# VIC20_SExp.net
KiCad netlist of a schematic drawn in EAGLE
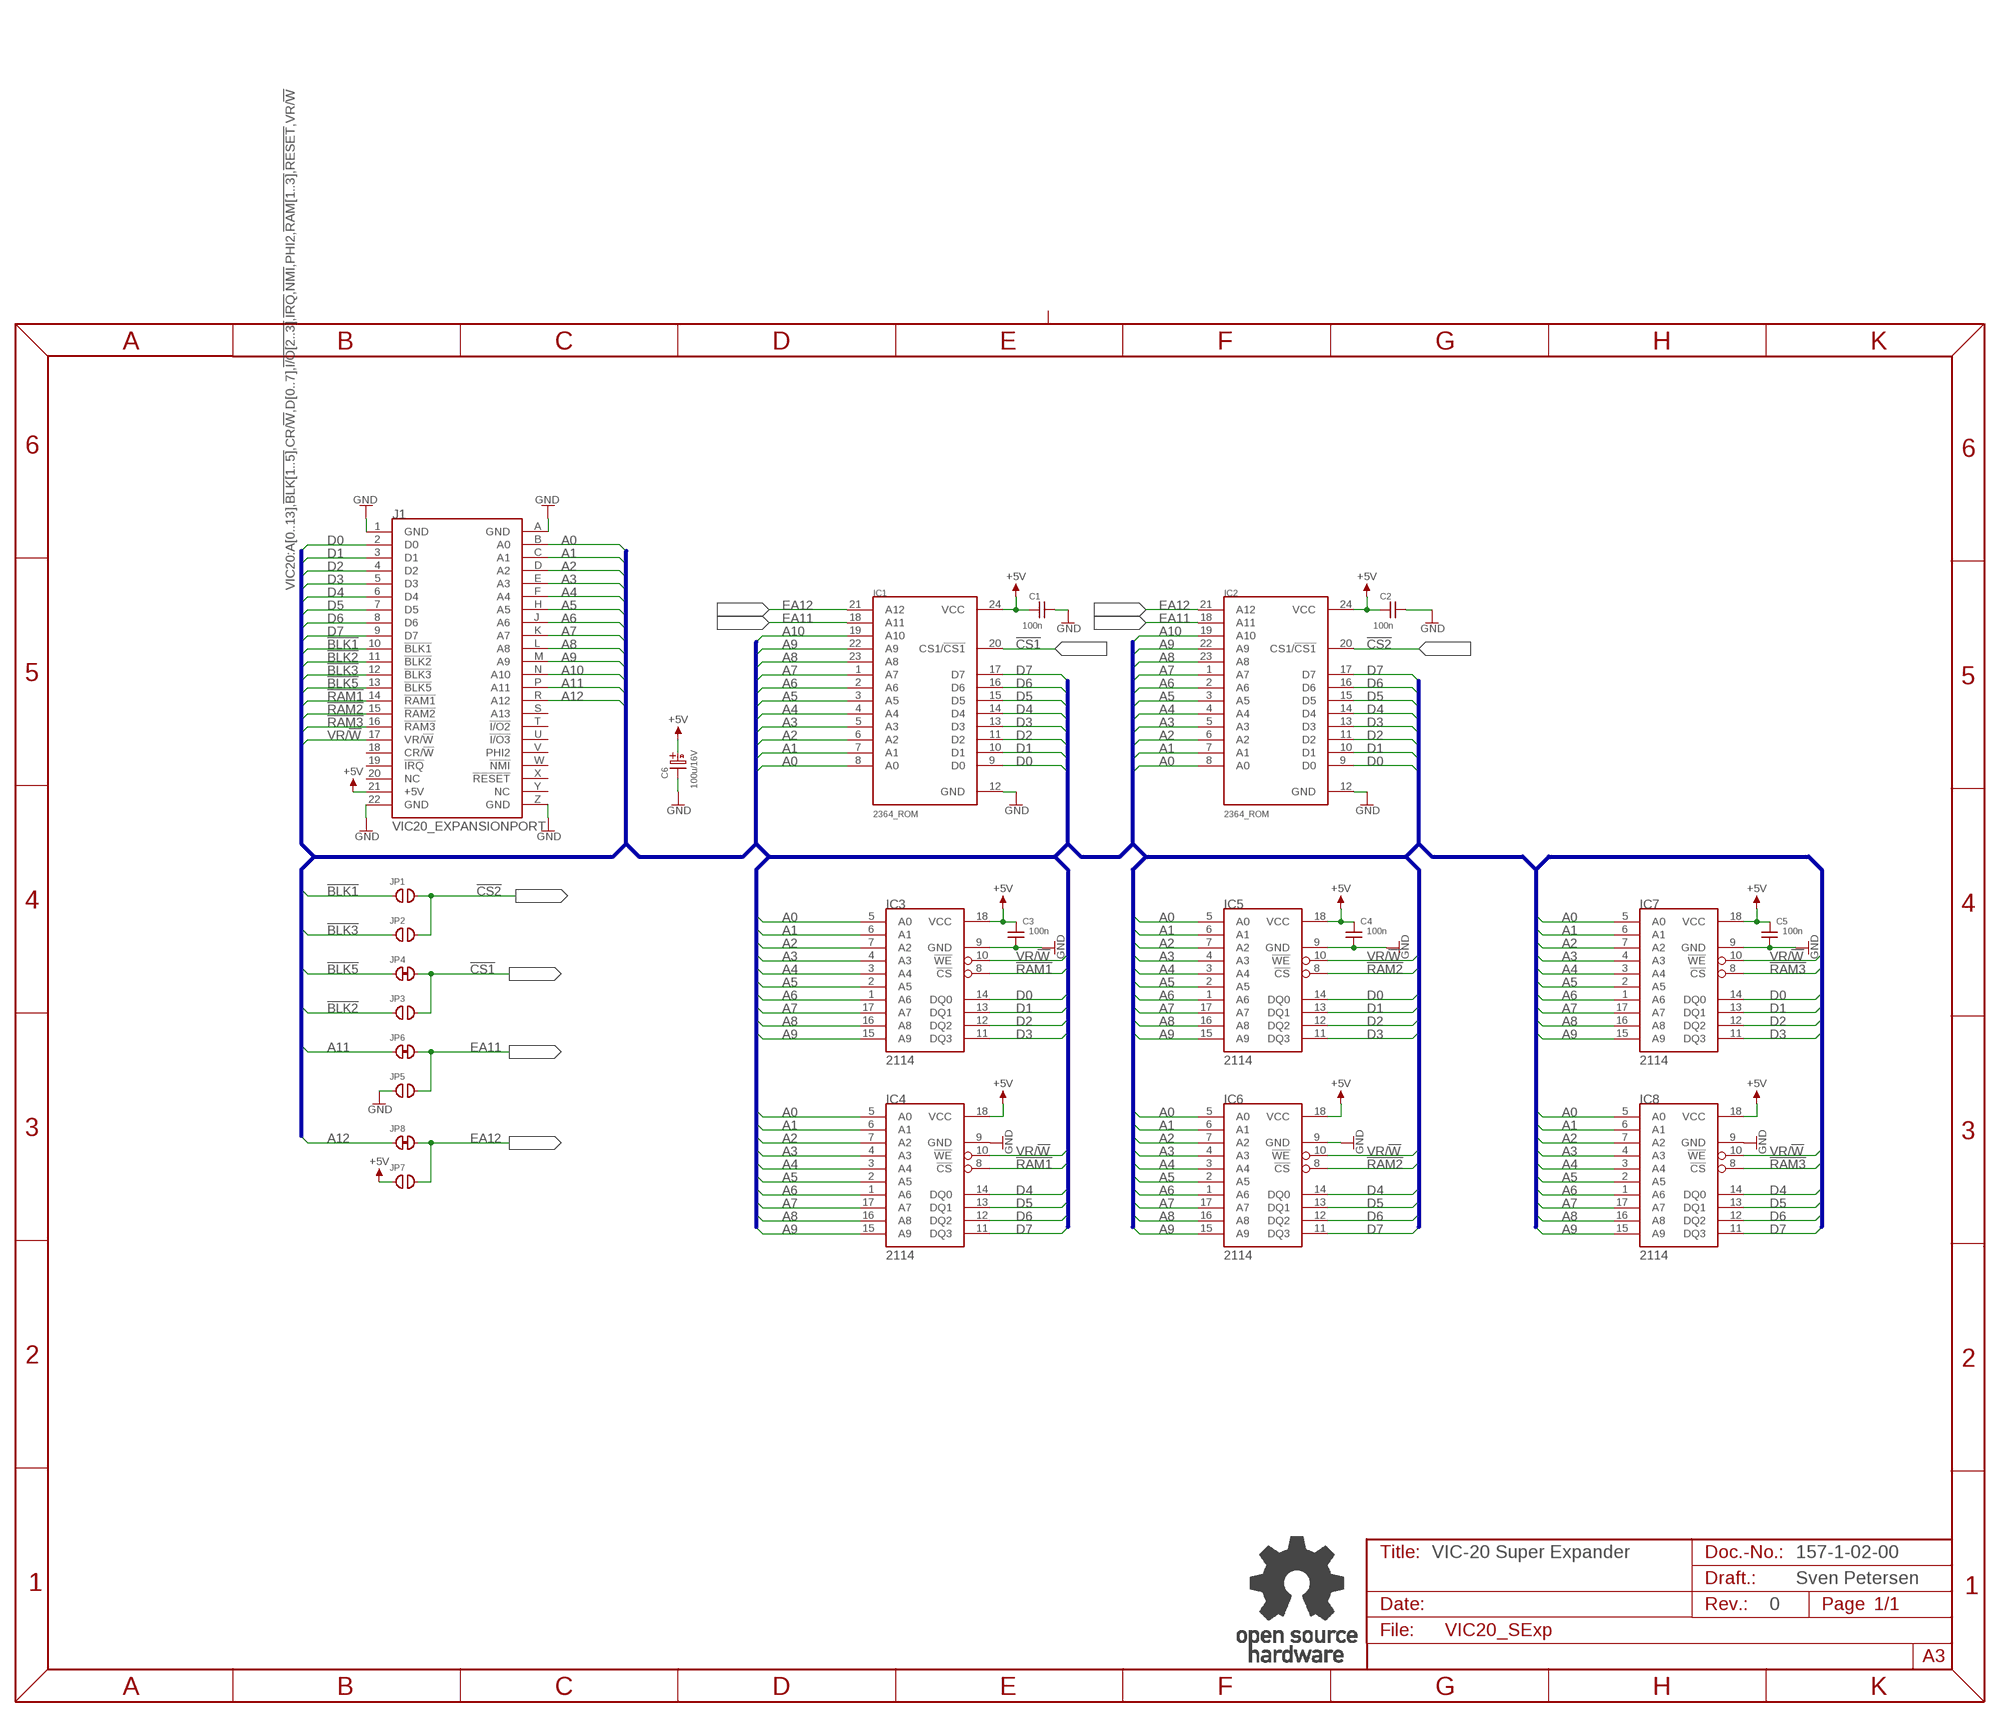
[diagram p0: schematic, sheet 1]

(export (version "E")
  (design (tool "Eeschema 10.0.6"))
  (components
    (comp (ref "C1")
      (value "100n")
      (footprint "eagle-import:C-2,5")
      (libsource (lib "eagle-import") (part "CAP01"))
    )
    (comp (ref "C2")
      (value "100n")
      (footprint "eagle-import:C-2,5")
      (libsource (lib "eagle-import") (part "CAP01"))
    )
    (comp (ref "C3")
      (value "100n")
      (footprint "eagle-import:C-2,5")
      (libsource (lib "eagle-import") (part "CAP01"))
    )
    (comp (ref "C4")
      (value "100n")
      (footprint "eagle-import:C-2,5")
      (libsource (lib "eagle-import") (part "CAP01"))
    )
    (comp (ref "C5")
      (value "100n")
      (footprint "eagle-import:C-2,5")
      (libsource (lib "eagle-import") (part "CAP01"))
    )
    (comp (ref "C6")
      (value "100u/16V")
      (footprint "eagle-import:C07_2,5")
      (libsource (lib "eagle-import") (part "C07/2,5"))
    )
    (comp (ref "IC1")
      (value "2364_ROM")
      (footprint "eagle-import:DIL24-6")
      (libsource (lib "eagle-import") (part "2364_ROM"))
    )
    (comp (ref "IC2")
      (value "2364_ROM")
      (footprint "eagle-import:DIL24-6")
      (libsource (lib "eagle-import") (part "2364_ROM"))
    )
    (comp (ref "IC3")
      (value "2114")
      (footprint "eagle-import:DIL18")
      (libsource (lib "eagle-import") (part "2114"))
    )
    (comp (ref "IC4")
      (value "2114")
      (footprint "eagle-import:DIL18")
      (libsource (lib "eagle-import") (part "2114"))
    )
    (comp (ref "IC5")
      (value "2114")
      (footprint "eagle-import:DIL18")
      (libsource (lib "eagle-import") (part "2114"))
    )
    (comp (ref "IC6")
      (value "2114")
      (footprint "eagle-import:DIL18")
      (libsource (lib "eagle-import") (part "2114"))
    )
    (comp (ref "IC7")
      (value "2114")
      (footprint "eagle-import:DIL18")
      (libsource (lib "eagle-import") (part "2114"))
    )
    (comp (ref "IC8")
      (value "2114")
      (footprint "eagle-import:DIL18")
      (libsource (lib "eagle-import") (part "2114"))
    )
    (comp (ref "J1")
      (value "VIC20_EXPANSIONPORT")
      (footprint "eagle-import:VIC20_EXPANSION")
      (libsource (lib "eagle-import") (part "VIC20_EXPANSIONPORT"))
    )
    (comp (ref "JP1")
      (value "OPEN")
      (footprint "eagle-import:CP_OP")
      (libsource (lib "eagle-import") (part "OPEN"))
    )
    (comp (ref "JP2")
      (value "OPEN")
      (footprint "eagle-import:CP_OP")
      (libsource (lib "eagle-import") (part "OPEN"))
    )
    (comp (ref "JP3")
      (value "OPEN")
      (footprint "eagle-import:CP_OP")
      (libsource (lib "eagle-import") (part "OPEN"))
    )
    (comp (ref "JP4")
      (value "CLOSED")
      (footprint "eagle-import:CP_CL")
      (libsource (lib "eagle-import") (part "CLOSED"))
    )
    (comp (ref "JP5")
      (value "OPEN")
      (footprint "eagle-import:CP_OP")
      (libsource (lib "eagle-import") (part "OPEN"))
    )
    (comp (ref "JP6")
      (value "CLOSED")
      (footprint "eagle-import:CP_CL")
      (libsource (lib "eagle-import") (part "CLOSED"))
    )
    (comp (ref "JP7")
      (value "OPEN")
      (footprint "eagle-import:CP_OP")
      (libsource (lib "eagle-import") (part "OPEN"))
    )
    (comp (ref "JP8")
      (value "CLOSED")
      (footprint "eagle-import:CP_CL")
      (libsource (lib "eagle-import") (part "CLOSED"))
    )
    (comp (ref "U$2")
      (value "OPEN_SOURCE_HW")
      (footprint "eagle-import:OPENHW")
      (libsource (lib "eagle-import") (part "OPEN_SOURCE_HW"))
    )
  )
  (nets
    (net (code "6") (name "+5V") (class "Default")
      (node (ref "C1") (pin "1") (pinfunction "1_1") (pintype "passive"))
      (node (ref "C2") (pin "1") (pinfunction "1_1") (pintype "passive"))
      (node (ref "C3") (pin "2") (pinfunction "2_2") (pintype "passive"))
      (node (ref "C4") (pin "2") (pinfunction "2_2") (pintype "passive"))
      (node (ref "C5") (pin "2") (pinfunction "2_2") (pintype "passive"))
      (node (ref "C6") (pin "A") (pinfunction "+_A") (pintype "passive"))
      (node (ref "IC1") (pin "24") (pinfunction "VCC_24") (pintype "power_in"))
      (node (ref "IC2") (pin "24") (pinfunction "VCC_24") (pintype "power_in"))
      (node (ref "IC3") (pin "18") (pinfunction "VCC_18") (pintype "power_in"))
      (node (ref "IC4") (pin "18") (pinfunction "VCC_18") (pintype "power_in"))
      (node (ref "IC5") (pin "18") (pinfunction "VCC_18") (pintype "power_in"))
      (node (ref "IC6") (pin "18") (pinfunction "VCC_18") (pintype "power_in"))
      (node (ref "IC7") (pin "18") (pinfunction "VCC_18") (pintype "power_in"))
      (node (ref "IC8") (pin "18") (pinfunction "VCC_18") (pintype "power_in"))
      (node (ref "J1") (pin "21") (pinfunction "+5V_21") (pintype "power_in"))
      (node (ref "JP7") (pin "1") (pinfunction "1_1") (pintype "passive"))
    )
    (net (code "7") (name "/A0") (class "Default")
      (node (ref "IC1") (pin "8") (pinfunction "A0_8") (pintype "input"))
      (node (ref "IC2") (pin "8") (pinfunction "A0_8") (pintype "input"))
      (node (ref "IC3") (pin "5") (pinfunction "A0_5") (pintype "input"))
      (node (ref "IC4") (pin "5") (pinfunction "A0_5") (pintype "input"))
      (node (ref "IC5") (pin "5") (pinfunction "A0_5") (pintype "input"))
      (node (ref "IC6") (pin "5") (pinfunction "A0_5") (pintype "input"))
      (node (ref "IC7") (pin "5") (pinfunction "A0_5") (pintype "input"))
      (node (ref "IC8") (pin "5") (pinfunction "A0_5") (pintype "input"))
      (node (ref "J1") (pin "B") (pinfunction "A0_B") (pintype "bidirectional"))
    )
    (net (code "8") (name "/A1") (class "Default")
      (node (ref "IC1") (pin "7") (pinfunction "A1_7") (pintype "input"))
      (node (ref "IC2") (pin "7") (pinfunction "A1_7") (pintype "input"))
      (node (ref "IC3") (pin "6") (pinfunction "A1_6") (pintype "input"))
      (node (ref "IC4") (pin "6") (pinfunction "A1_6") (pintype "input"))
      (node (ref "IC5") (pin "6") (pinfunction "A1_6") (pintype "input"))
      (node (ref "IC6") (pin "6") (pinfunction "A1_6") (pintype "input"))
      (node (ref "IC7") (pin "6") (pinfunction "A1_6") (pintype "input"))
      (node (ref "IC8") (pin "6") (pinfunction "A1_6") (pintype "input"))
      (node (ref "J1") (pin "C") (pinfunction "A1_C") (pintype "bidirectional"))
    )
    (net (code "9") (name "/A2") (class "Default")
      (node (ref "IC1") (pin "6") (pinfunction "A2_6") (pintype "input"))
      (node (ref "IC2") (pin "6") (pinfunction "A2_6") (pintype "input"))
      (node (ref "IC3") (pin "7") (pinfunction "A2_7") (pintype "input"))
      (node (ref "IC4") (pin "7") (pinfunction "A2_7") (pintype "input"))
      (node (ref "IC5") (pin "7") (pinfunction "A2_7") (pintype "input"))
      (node (ref "IC6") (pin "7") (pinfunction "A2_7") (pintype "input"))
      (node (ref "IC7") (pin "7") (pinfunction "A2_7") (pintype "input"))
      (node (ref "IC8") (pin "7") (pinfunction "A2_7") (pintype "input"))
      (node (ref "J1") (pin "D") (pinfunction "A2_D") (pintype "bidirectional"))
    )
    (net (code "10") (name "/A3") (class "Default")
      (node (ref "IC1") (pin "5") (pinfunction "A3_5") (pintype "input"))
      (node (ref "IC2") (pin "5") (pinfunction "A3_5") (pintype "input"))
      (node (ref "IC3") (pin "4") (pinfunction "A3_4") (pintype "input"))
      (node (ref "IC4") (pin "4") (pinfunction "A3_4") (pintype "input"))
      (node (ref "IC5") (pin "4") (pinfunction "A3_4") (pintype "input"))
      (node (ref "IC6") (pin "4") (pinfunction "A3_4") (pintype "input"))
      (node (ref "IC7") (pin "4") (pinfunction "A3_4") (pintype "input"))
      (node (ref "IC8") (pin "4") (pinfunction "A3_4") (pintype "input"))
      (node (ref "J1") (pin "E") (pinfunction "A3_E") (pintype "bidirectional"))
    )
    (net (code "11") (name "/A4") (class "Default")
      (node (ref "IC1") (pin "4") (pinfunction "A4_4") (pintype "input"))
      (node (ref "IC2") (pin "4") (pinfunction "A4_4") (pintype "input"))
      (node (ref "IC3") (pin "3") (pinfunction "A4_3") (pintype "input"))
      (node (ref "IC4") (pin "3") (pinfunction "A4_3") (pintype "input"))
      (node (ref "IC5") (pin "3") (pinfunction "A4_3") (pintype "input"))
      (node (ref "IC6") (pin "3") (pinfunction "A4_3") (pintype "input"))
      (node (ref "IC7") (pin "3") (pinfunction "A4_3") (pintype "input"))
      (node (ref "IC8") (pin "3") (pinfunction "A4_3") (pintype "input"))
      (node (ref "J1") (pin "F") (pinfunction "A4_F") (pintype "bidirectional"))
    )
    (net (code "12") (name "/A5") (class "Default")
      (node (ref "IC1") (pin "3") (pinfunction "A5_3") (pintype "input"))
      (node (ref "IC2") (pin "3") (pinfunction "A5_3") (pintype "input"))
      (node (ref "IC3") (pin "2") (pinfunction "A5_2") (pintype "input"))
      (node (ref "IC4") (pin "2") (pinfunction "A5_2") (pintype "input"))
      (node (ref "IC5") (pin "2") (pinfunction "A5_2") (pintype "input"))
      (node (ref "IC6") (pin "2") (pinfunction "A5_2") (pintype "input"))
      (node (ref "IC7") (pin "2") (pinfunction "A5_2") (pintype "input"))
      (node (ref "IC8") (pin "2") (pinfunction "A5_2") (pintype "input"))
      (node (ref "J1") (pin "H") (pinfunction "A5_H") (pintype "bidirectional"))
    )
    (net (code "13") (name "/A6") (class "Default")
      (node (ref "IC1") (pin "2") (pinfunction "A6_2") (pintype "input"))
      (node (ref "IC2") (pin "2") (pinfunction "A6_2") (pintype "input"))
      (node (ref "IC3") (pin "1") (pinfunction "A6_1") (pintype "input"))
      (node (ref "IC4") (pin "1") (pinfunction "A6_1") (pintype "input"))
      (node (ref "IC5") (pin "1") (pinfunction "A6_1") (pintype "input"))
      (node (ref "IC6") (pin "1") (pinfunction "A6_1") (pintype "input"))
      (node (ref "IC7") (pin "1") (pinfunction "A6_1") (pintype "input"))
      (node (ref "IC8") (pin "1") (pinfunction "A6_1") (pintype "input"))
      (node (ref "J1") (pin "J") (pinfunction "A6_J") (pintype "bidirectional"))
    )
    (net (code "14") (name "/A7") (class "Default")
      (node (ref "IC1") (pin "1") (pinfunction "A7_1") (pintype "input"))
      (node (ref "IC2") (pin "1") (pinfunction "A7_1") (pintype "input"))
      (node (ref "IC3") (pin "17") (pinfunction "A7_17") (pintype "input"))
      (node (ref "IC4") (pin "17") (pinfunction "A7_17") (pintype "input"))
      (node (ref "IC5") (pin "17") (pinfunction "A7_17") (pintype "input"))
      (node (ref "IC6") (pin "17") (pinfunction "A7_17") (pintype "input"))
      (node (ref "IC7") (pin "17") (pinfunction "A7_17") (pintype "input"))
      (node (ref "IC8") (pin "17") (pinfunction "A7_17") (pintype "input"))
      (node (ref "J1") (pin "K") (pinfunction "A7_K") (pintype "bidirectional"))
    )
    (net (code "15") (name "/A8") (class "Default")
      (node (ref "IC1") (pin "23") (pinfunction "A8_23") (pintype "input"))
      (node (ref "IC2") (pin "23") (pinfunction "A8_23") (pintype "input"))
      (node (ref "IC3") (pin "16") (pinfunction "A8_16") (pintype "input"))
      (node (ref "IC4") (pin "16") (pinfunction "A8_16") (pintype "input"))
      (node (ref "IC5") (pin "16") (pinfunction "A8_16") (pintype "input"))
      (node (ref "IC6") (pin "16") (pinfunction "A8_16") (pintype "input"))
      (node (ref "IC7") (pin "16") (pinfunction "A8_16") (pintype "input"))
      (node (ref "IC8") (pin "16") (pinfunction "A8_16") (pintype "input"))
      (node (ref "J1") (pin "L") (pinfunction "A8_L") (pintype "bidirectional"))
    )
    (net (code "16") (name "/A9") (class "Default")
      (node (ref "IC1") (pin "22") (pinfunction "A9_22") (pintype "input"))
      (node (ref "IC2") (pin "22") (pinfunction "A9_22") (pintype "input"))
      (node (ref "IC3") (pin "15") (pinfunction "A9_15") (pintype "input"))
      (node (ref "IC4") (pin "15") (pinfunction "A9_15") (pintype "input"))
      (node (ref "IC5") (pin "15") (pinfunction "A9_15") (pintype "input"))
      (node (ref "IC6") (pin "15") (pinfunction "A9_15") (pintype "input"))
      (node (ref "IC7") (pin "15") (pinfunction "A9_15") (pintype "input"))
      (node (ref "IC8") (pin "15") (pinfunction "A9_15") (pintype "input"))
      (node (ref "J1") (pin "M") (pinfunction "A9_M") (pintype "bidirectional"))
    )
    (net (code "17") (name "/A10") (class "Default")
      (node (ref "IC1") (pin "19") (pinfunction "A10_19") (pintype "input"))
      (node (ref "IC2") (pin "19") (pinfunction "A10_19") (pintype "input"))
      (node (ref "J1") (pin "N") (pinfunction "A10_N") (pintype "bidirectional"))
    )
    (net (code "18") (name "/A11") (class "Default")
      (node (ref "J1") (pin "P") (pinfunction "A11_P") (pintype "bidirectional"))
      (node (ref "JP6") (pin "1") (pinfunction "1_1") (pintype "passive"))
    )
    (net (code "19") (name "/A12") (class "Default")
      (node (ref "J1") (pin "R") (pinfunction "A12_R") (pintype "bidirectional"))
      (node (ref "JP8") (pin "1") (pinfunction "1_1") (pintype "passive"))
    )
    (net (code "20") (name "/D0") (class "Default")
      (node (ref "IC1") (pin "9") (pinfunction "D0_9") (pintype "tri_state"))
      (node (ref "IC2") (pin "9") (pinfunction "D0_9") (pintype "tri_state"))
      (node (ref "IC3") (pin "14") (pinfunction "DQ0_14") (pintype "bidirectional"))
      (node (ref "IC5") (pin "14") (pinfunction "DQ0_14") (pintype "bidirectional"))
      (node (ref "IC7") (pin "14") (pinfunction "DQ0_14") (pintype "bidirectional"))
      (node (ref "J1") (pin "2") (pinfunction "D0_2") (pintype "bidirectional"))
    )
    (net (code "21") (name "/D1") (class "Default")
      (node (ref "IC1") (pin "10") (pinfunction "D1_10") (pintype "tri_state"))
      (node (ref "IC2") (pin "10") (pinfunction "D1_10") (pintype "tri_state"))
      (node (ref "IC3") (pin "13") (pinfunction "DQ1_13") (pintype "bidirectional"))
      (node (ref "IC5") (pin "13") (pinfunction "DQ1_13") (pintype "bidirectional"))
      (node (ref "IC7") (pin "13") (pinfunction "DQ1_13") (pintype "bidirectional"))
      (node (ref "J1") (pin "3") (pinfunction "D1_3") (pintype "bidirectional"))
    )
    (net (code "22") (name "/D2") (class "Default")
      (node (ref "IC1") (pin "11") (pinfunction "D2_11") (pintype "tri_state"))
      (node (ref "IC2") (pin "11") (pinfunction "D2_11") (pintype "tri_state"))
      (node (ref "IC3") (pin "12") (pinfunction "DQ2_12") (pintype "bidirectional"))
      (node (ref "IC5") (pin "12") (pinfunction "DQ2_12") (pintype "bidirectional"))
      (node (ref "IC7") (pin "12") (pinfunction "DQ2_12") (pintype "bidirectional"))
      (node (ref "J1") (pin "4") (pinfunction "D2_4") (pintype "bidirectional"))
    )
    (net (code "23") (name "/D3") (class "Default")
      (node (ref "IC1") (pin "13") (pinfunction "D3_13") (pintype "tri_state"))
      (node (ref "IC2") (pin "13") (pinfunction "D3_13") (pintype "tri_state"))
      (node (ref "IC3") (pin "11") (pinfunction "DQ3_11") (pintype "bidirectional"))
      (node (ref "IC5") (pin "11") (pinfunction "DQ3_11") (pintype "bidirectional"))
      (node (ref "IC7") (pin "11") (pinfunction "DQ3_11") (pintype "bidirectional"))
      (node (ref "J1") (pin "5") (pinfunction "D3_5") (pintype "bidirectional"))
    )
    (net (code "24") (name "/D4") (class "Default")
      (node (ref "IC1") (pin "14") (pinfunction "D4_14") (pintype "tri_state"))
      (node (ref "IC2") (pin "14") (pinfunction "D4_14") (pintype "tri_state"))
      (node (ref "IC4") (pin "14") (pinfunction "DQ0_14") (pintype "bidirectional"))
      (node (ref "IC6") (pin "14") (pinfunction "DQ0_14") (pintype "bidirectional"))
      (node (ref "IC8") (pin "14") (pinfunction "DQ0_14") (pintype "bidirectional"))
      (node (ref "J1") (pin "6") (pinfunction "D4_6") (pintype "bidirectional"))
    )
    (net (code "25") (name "/D5") (class "Default")
      (node (ref "IC1") (pin "15") (pinfunction "D5_15") (pintype "tri_state"))
      (node (ref "IC2") (pin "15") (pinfunction "D5_15") (pintype "tri_state"))
      (node (ref "IC4") (pin "13") (pinfunction "DQ1_13") (pintype "bidirectional"))
      (node (ref "IC6") (pin "13") (pinfunction "DQ1_13") (pintype "bidirectional"))
      (node (ref "IC8") (pin "13") (pinfunction "DQ1_13") (pintype "bidirectional"))
      (node (ref "J1") (pin "7") (pinfunction "D5_7") (pintype "bidirectional"))
    )
    (net (code "26") (name "/D6") (class "Default")
      (node (ref "IC1") (pin "16") (pinfunction "D6_16") (pintype "tri_state"))
      (node (ref "IC2") (pin "16") (pinfunction "D6_16") (pintype "tri_state"))
      (node (ref "IC4") (pin "12") (pinfunction "DQ2_12") (pintype "bidirectional"))
      (node (ref "IC6") (pin "12") (pinfunction "DQ2_12") (pintype "bidirectional"))
      (node (ref "IC8") (pin "12") (pinfunction "DQ2_12") (pintype "bidirectional"))
      (node (ref "J1") (pin "8") (pinfunction "D6_8") (pintype "bidirectional"))
    )
    (net (code "27") (name "/D7") (class "Default")
      (node (ref "IC1") (pin "17") (pinfunction "D7_17") (pintype "tri_state"))
      (node (ref "IC2") (pin "17") (pinfunction "D7_17") (pintype "tri_state"))
      (node (ref "IC4") (pin "11") (pinfunction "DQ3_11") (pintype "bidirectional"))
      (node (ref "IC6") (pin "11") (pinfunction "DQ3_11") (pintype "bidirectional"))
      (node (ref "IC8") (pin "11") (pinfunction "DQ3_11") (pintype "bidirectional"))
      (node (ref "J1") (pin "9") (pinfunction "D7_9") (pintype "bidirectional"))
    )
    (net (code "28") (name "/EA11") (class "Default")
      (node (ref "IC1") (pin "18") (pinfunction "A11_18") (pintype "input"))
      (node (ref "IC2") (pin "18") (pinfunction "A11_18") (pintype "input"))
      (node (ref "JP5") (pin "2") (pinfunction "2_2") (pintype "passive"))
      (node (ref "JP6") (pin "2") (pinfunction "2_2") (pintype "passive"))
    )
    (net (code "29") (name "/EA12") (class "Default")
      (node (ref "IC1") (pin "21") (pinfunction "A12_21") (pintype "input"))
      (node (ref "IC2") (pin "21") (pinfunction "A12_21") (pintype "input"))
      (node (ref "JP7") (pin "2") (pinfunction "2_2") (pintype "passive"))
      (node (ref "JP8") (pin "2") (pinfunction "2_2") (pintype "passive"))
    )
    (net (code "30") (name "/NC") (class "Default")
      (node (ref "J1") (pin "20") (pinfunction "NC_20") (pintype "power_in"))
    )
    (net (code "31") (name "/VR{slash}~{W}") (class "Default")
      (node (ref "IC3") (pin "10") (pinfunction "~{WE}_10") (pintype "input"))
      (node (ref "IC4") (pin "10") (pinfunction "~{WE}_10") (pintype "input"))
      (node (ref "IC5") (pin "10") (pinfunction "~{WE}_10") (pintype "input"))
      (node (ref "IC6") (pin "10") (pinfunction "~{WE}_10") (pintype "input"))
      (node (ref "IC7") (pin "10") (pinfunction "~{WE}_10") (pintype "input"))
      (node (ref "IC8") (pin "10") (pinfunction "~{WE}_10") (pintype "input"))
      (node (ref "J1") (pin "17") (pinfunction "VR/~{W}_17") (pintype "output"))
    )
    (net (code "33") (name "/~{BLK1}") (class "Default")
      (node (ref "J1") (pin "10") (pinfunction "~{BLK1}_10") (pintype "input"))
      (node (ref "JP1") (pin "1") (pinfunction "1_1") (pintype "passive"))
    )
    (net (code "34") (name "/~{BLK2}") (class "Default")
      (node (ref "J1") (pin "11") (pinfunction "~{BLK2}_11") (pintype "input"))
      (node (ref "JP3") (pin "1") (pinfunction "1_1") (pintype "passive"))
    )
    (net (code "35") (name "/~{BLK3}") (class "Default")
      (node (ref "J1") (pin "12") (pinfunction "~{BLK3}_12") (pintype "output"))
      (node (ref "JP2") (pin "1") (pinfunction "1_1") (pintype "passive"))
    )
    (net (code "36") (name "/~{BLK5}") (class "Default")
      (node (ref "J1") (pin "13") (pinfunction "~{BLK5}_13") (pintype "output"))
      (node (ref "JP4") (pin "1") (pinfunction "1_1") (pintype "passive"))
    )
    (net (code "37") (name "/~{CS1}") (class "Default")
      (node (ref "IC1") (pin "20") (pinfunction "CS1/~{CS1}_20") (pintype "input"))
      (node (ref "JP3") (pin "2") (pinfunction "2_2") (pintype "passive"))
      (node (ref "JP4") (pin "2") (pinfunction "2_2") (pintype "passive"))
    )
    (net (code "38") (name "/~{CS2}") (class "Default")
      (node (ref "IC2") (pin "20") (pinfunction "CS1/~{CS1}_20") (pintype "input"))
      (node (ref "JP1") (pin "2") (pinfunction "2_2") (pintype "passive"))
      (node (ref "JP2") (pin "2") (pinfunction "2_2") (pintype "passive"))
    )
    (net (code "39") (name "/~{RAM1}") (class "Default")
      (node (ref "IC3") (pin "8") (pinfunction "~{CS}_8") (pintype "input"))
      (node (ref "IC4") (pin "8") (pinfunction "~{CS}_8") (pintype "input"))
      (node (ref "J1") (pin "14") (pinfunction "~{RAM1}_14") (pintype "input"))
    )
    (net (code "40") (name "/~{RAM2}") (class "Default")
      (node (ref "IC5") (pin "8") (pinfunction "~{CS}_8") (pintype "input"))
      (node (ref "IC6") (pin "8") (pinfunction "~{CS}_8") (pintype "input"))
      (node (ref "J1") (pin "15") (pinfunction "~{RAM2}_15") (pintype "output"))
    )
    (net (code "41") (name "/~{RAM3}") (class "Default")
      (node (ref "IC7") (pin "8") (pinfunction "~{CS}_8") (pintype "input"))
      (node (ref "IC8") (pin "8") (pinfunction "~{CS}_8") (pintype "input"))
      (node (ref "J1") (pin "16") (pinfunction "~{RAM3}_16") (pintype "output"))
    )
    (net (code "42") (name "GND") (class "Default")
      (node (ref "C1") (pin "2") (pinfunction "2_2") (pintype "passive"))
      (node (ref "C2") (pin "2") (pinfunction "2_2") (pintype "passive"))
      (node (ref "C3") (pin "1") (pinfunction "1_1") (pintype "passive"))
      (node (ref "C4") (pin "1") (pinfunction "1_1") (pintype "passive"))
      (node (ref "C5") (pin "1") (pinfunction "1_1") (pintype "passive"))
      (node (ref "C6") (pin "K") (pinfunction "-_K") (pintype "passive"))
      (node (ref "IC1") (pin "12") (pinfunction "GND_12") (pintype "power_in"))
      (node (ref "IC2") (pin "12") (pinfunction "GND_12") (pintype "power_in"))
      (node (ref "IC3") (pin "9") (pinfunction "GND_9") (pintype "power_in"))
      (node (ref "IC4") (pin "9") (pinfunction "GND_9") (pintype "power_in"))
      (node (ref "IC5") (pin "9") (pinfunction "GND_9") (pintype "power_in"))
      (node (ref "IC6") (pin "9") (pinfunction "GND_9") (pintype "power_in"))
      (node (ref "IC7") (pin "9") (pinfunction "GND_9") (pintype "power_in"))
      (node (ref "IC8") (pin "9") (pinfunction "GND_9") (pintype "power_in"))
      (node (ref "J1") (pin "1") (pinfunction "GND_1") (pintype "power_in"))
      (node (ref "J1") (pin "22") (pinfunction "GND_22") (pintype "power_in"))
      (node (ref "J1") (pin "A") (pinfunction "GND_A") (pintype "power_in"))
      (node (ref "J1") (pin "Z") (pinfunction "GND_Z") (pintype "power_in"))
      (node (ref "JP5") (pin "1") (pinfunction "1_1") (pintype "passive"))
    )
    (net (code "43") (name "unconnected-(J1-A13-PadS)") (class "Default")
      (node (ref "J1") (pin "S") (pinfunction "A13_S") (pintype "bidirectional"))
    )
    (net (code "44") (name "unconnected-(J1-CR{slash}~{W}-Pad18)") (class "Default")
      (node (ref "J1") (pin "18") (pinfunction "CR/~{W}_18") (pintype "output"))
    )
    (net (code "45") (name "unconnected-(J1-NC-PadY)") (class "Default")
      (node (ref "J1") (pin "Y") (pinfunction "NC_Y") (pintype "bidirectional"))
    )
    (net (code "46") (name "unconnected-(J1-PHI2-PadV)") (class "Default")
      (node (ref "J1") (pin "V") (pinfunction "PHI2_V") (pintype "bidirectional"))
    )
    (net (code "47") (name "unconnected-(J1-~{IRQ}-Pad19)") (class "Default")
      (node (ref "J1") (pin "19") (pinfunction "~{IRQ}_19") (pintype "input"))
    )
    (net (code "48") (name "unconnected-(J1-~{I{slash}O2}-PadT)") (class "Default")
      (node (ref "J1") (pin "T") (pinfunction "~{I/O2}_T") (pintype "output"))
    )
    (net (code "49") (name "unconnected-(J1-~{I{slash}O3}-PadU)") (class "Default")
      (node (ref "J1") (pin "U") (pinfunction "~{I/O3}_U") (pintype "output"))
    )
    (net (code "50") (name "unconnected-(J1-~{NMI}-PadW)") (class "Default")
      (node (ref "J1") (pin "W") (pinfunction "~{NMI}_W") (pintype "input"))
    )
    (net (code "51") (name "unconnected-(J1-~{RESET}-PadX)") (class "Default")
      (node (ref "J1") (pin "X") (pinfunction "~{RESET}_X") (pintype "open_collector"))
    )
  )
)
